# PSU.net
KiCad netlist of a schematic drawn in Altium Designer
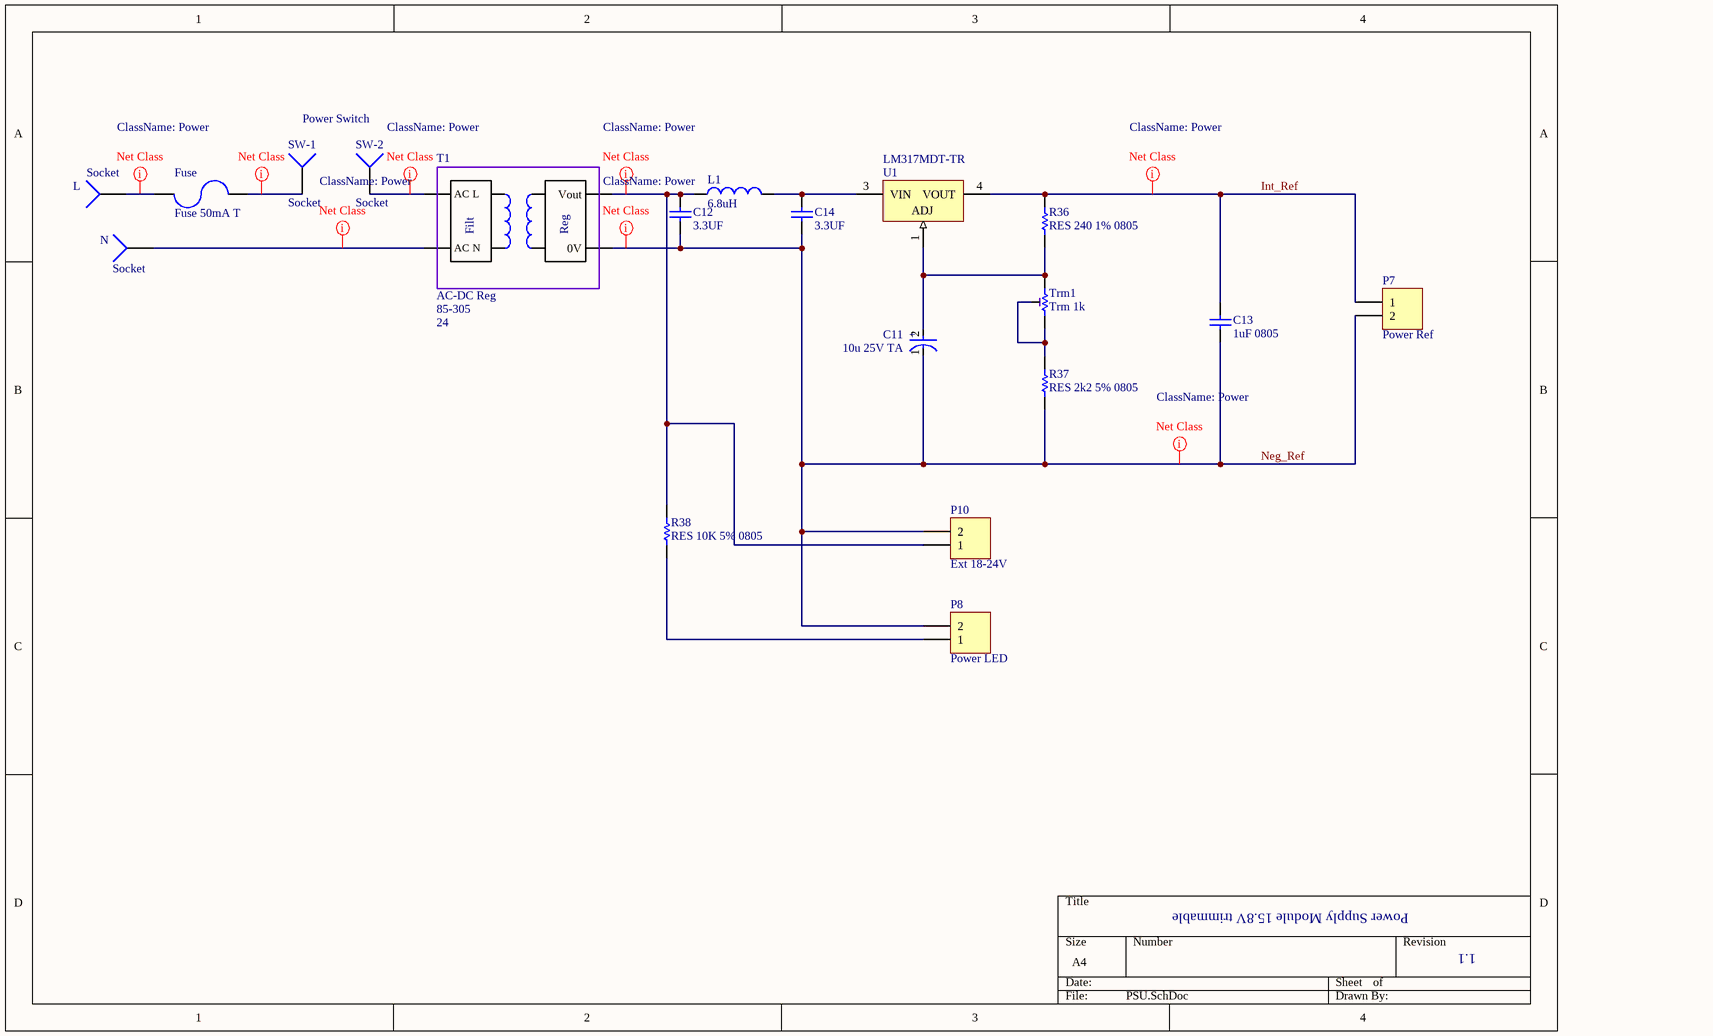
[diagram p0: PSU.SchDoc]

(export (version "E")
  (design (tool "Eeschema 10.0.6"))
  (components
    (comp (ref "C11")
      (value "10u 25V TA")
      (footprint "FP-TPE-D4-MFG")
      (description "CAP TANT 10u 25V")
      (fields (field (name "TOLERANCE") "20%") (field (name "MANUFACTURER PART NUMBER") "6TPE330MAA"))
      (libsource (lib "Altium Content Vault") (part "CMP-05428-000010-1"))
    )
    (comp (ref "C12")
      (value "3.3UF")
      (footprint "CAPC1206(3216)150_L")
      (description "1206 (3216 Metric) Chip Capacitor")
      (libsource (lib "Altium Content Vault") (part "CMP-1590-00001-1"))
    )
    (comp (ref "C13")
      (value "1uF 0805")
      (footprint "CAPC2113X88X50NL30T25")
      (fields (field (name "MANUFACTURER") "Kemet") (field (name "PART NUMBER") "C0805X474K4RACTU"))
      (libsource (lib "Altium Content Vault") (part "CMP-2007-00001-1"))
    )
    (comp (ref "C14")
      (value "3.3UF")
      (footprint "CAPC1206(3216)150_L")
      (description "1206 (3216 Metric) Chip Capacitor")
      (libsource (lib "Altium Content Vault") (part "CMP-1590-00001-1"))
    )
    (comp (ref "Fuse")
      (value "Fuse 50mA T")
      (footprint "Fuse Holder 20mm PCB with Cover")
      (description "Fuse")
      (libsource (lib "Mechanical") (part "Fuse"))
    )
    (comp (ref "L")
      (value "Socket")
      (footprint "PIN1")
      (fields (field (name "PUBLISHER") "Altium Limited"))
      (libsource (lib "Miscellaneous Connectors") (part "Socket"))
    )
    (comp (ref "L1")
      (value "6.8uH")
      (footprint "2.5x2 Inductor")
      (description "Inductor 6.8uH")
      (libsource (lib "Pref Passive") (part "Inductor"))
    )
    (comp (ref "N")
      (value "Socket")
      (footprint "PIN1")
      (fields (field (name "PUBLISHER") "Altium Limited"))
      (libsource (lib "Miscellaneous Connectors") (part "Socket"))
    )
    (comp (ref "P7")
      (value "Power Ref")
      (footprint "HDR1X2")
      (description "Header, 2-Pin")
      (fields (field (name "PUBLISHER") "Altium Limited"))
      (libsource (lib "Miscellaneous Connectors") (part "Header 2"))
    )
    (comp (ref "P8")
      (value "Power LED")
      (footprint "HDR1X2")
      (description "Header, 2-Pin")
      (fields (field (name "PUBLISHER") "Altium Limited"))
      (libsource (lib "") (part "Header 2_1"))
    )
    (comp (ref "P10")
      (value "Ext 18-24V")
      (footprint "HDR1X2")
      (description "Header, 2-Pin")
      (fields (field (name "PUBLISHER") "Altium Limited"))
      (libsource (lib "") (part "Header 2_1"))
    )
    (comp (ref "R36")
      (value "RES 240 1% 0805")
      (footprint "RESC2013X70X40LL20T20")
      (description "Resistor 240 1% 0805  0.2W 10ppm/C")
      (fields (field (name "MANUFACTURER") "Panasonic"))
      (libsource (lib "Altium Content Vault") (part "CMP-2001-00110-5"))
    )
    (comp (ref "R37")
      (value "RES 2k2 5% 0805")
      (footprint "RESC2013X70X40LL20T20")
      (description "Resistor 2k2 5% 0805  0.2W 10ppm/C")
      (fields (field (name "MANUFACTURER") "Panasonic"))
      (libsource (lib "Altium Content Vault") (part "CMP-2001-00110-5"))
    )
    (comp (ref "R38")
      (value "RES 10K 5% 0805")
      (footprint "RESC2013X70X40LL20T20")
      (description "Resistor 10K 5% 0805  0.2W 50ppm/C")
      (fields (field (name "MANUFACTURER") "Panasonic"))
      (libsource (lib "Altium Content Vault") (part "CMP-2001-00110-5"))
    )
    (comp (ref "SW-1")
      (value "Socket")
      (footprint "PIN1")
      (fields (field (name "PUBLISHER") "Altium Limited"))
      (libsource (lib "Miscellaneous Connectors") (part "Socket"))
    )
    (comp (ref "SW-2")
      (value "Socket")
      (footprint "PIN1")
      (fields (field (name "PUBLISHER") "Altium Limited"))
      (libsource (lib "Miscellaneous Connectors") (part "Socket"))
    )
    (comp (ref "T1")
      (value "AC-DC Reg")
      (footprint "IRM-02 Moule SM")
      (description "AC-DC Regulated Module 24V")
      (fields (field (name "VACIN") "85-305") (field (name "VDC OUT") "24"))
      (libsource (lib "Power Module") (part "AC-DC Reg Module"))
    )
    (comp (ref "Trm1")
      (value "Trm 1k")
      (footprint "3214W Trimmer")
      (description "Trimmer")
      (libsource (lib "Pref Passive") (part "Trimmer"))
    )
    (comp (ref "U1")
      (value "LM317MDT-TR")
      (footprint "TO-252_L")
      (description "500mA, Medium Current 1.2 to 37 V Adjustable Voltage Regulator, 3-Pin DPAK, Tape and Reel")
      (libsource (lib "Altium Content Vault") (part "CMP-0244-00074-1"))
    )
  )
  (nets
    (net (code "1") (name "/Int_Ref") (class "Default")
      (node (ref "C13") (pin "1") (pinfunction "1_1") (pintype "passive"))
      (node (ref "P7") (pin "1") (pinfunction "1_1") (pintype "passive"))
      (node (ref "R36") (pin "2") (pinfunction "2_2") (pintype "passive"))
      (node (ref "U1") (pin "4") (pinfunction "VOUT_4") (pintype "power_in"))
    )
    (net (code "2") (name "/Neg_Ref") (class "Default")
      (node (ref "C11") (pin "1") (pinfunction "C_1") (pintype "passive"))
      (node (ref "C12") (pin "1") (pinfunction "1_1") (pintype "passive"))
      (node (ref "C13") (pin "2") (pinfunction "2_2") (pintype "passive"))
      (node (ref "C14") (pin "1") (pinfunction "1_1") (pintype "passive"))
      (node (ref "P10") (pin "2") (pinfunction "2_2") (pintype "passive"))
      (node (ref "P7") (pin "2") (pinfunction "2_2") (pintype "passive"))
      (node (ref "P8") (pin "2") (pinfunction "2_2") (pintype "passive"))
      (node (ref "R37") (pin "1") (pinfunction "1_1") (pintype "passive"))
      (node (ref "T1") (pin "0V") (pinfunction "0V_0V") (pintype "power_in"))
    )
    (net (code "3") (name "Net-(C11-A)") (class "Default")
      (node (ref "C11") (pin "2") (pinfunction "A_2") (pintype "passive"))
      (node (ref "R36") (pin "1") (pinfunction "1_1") (pintype "passive"))
      (node (ref "Trm1") (pin "3") (pinfunction "3_3") (pintype "passive"))
      (node (ref "U1") (pin "1") (pinfunction "ADJ_1") (pintype "input"))
    )
    (net (code "4") (name "Net-(C12-Pad2)") (class "Default")
      (node (ref "C12") (pin "2") (pinfunction "2_2") (pintype "passive"))
      (node (ref "L1") (pin "1") (pinfunction "1_1") (pintype "passive"))
      (node (ref "P10") (pin "1") (pinfunction "1_1") (pintype "passive"))
      (node (ref "R38") (pin "2") (pinfunction "2_2") (pintype "passive"))
      (node (ref "T1") (pin "Vout") (pinfunction "Vout_Vout") (pintype "power_in"))
    )
    (net (code "5") (name "Net-(Fuse-Pad1)") (class "Default")
      (node (ref "Fuse") (pin "1") (pinfunction "1_1") (pintype "passive"))
      (node (ref "L") (pin "1") (pinfunction "1_1") (pintype "passive"))
    )
    (net (code "6") (name "Net-(Fuse-Pad2)") (class "Default")
      (node (ref "Fuse") (pin "2") (pinfunction "2_2") (pintype "passive"))
      (node (ref "SW-1") (pin "1") (pinfunction "1_1") (pintype "passive"))
    )
    (net (code "7") (name "Net-(P8-Pad1)") (class "Default")
      (node (ref "P8") (pin "1") (pinfunction "1_1") (pintype "passive"))
      (node (ref "R38") (pin "1") (pinfunction "1_1") (pintype "passive"))
    )
    (net (code "8") (name "Net-(R37-Pad2)") (class "Default")
      (node (ref "R37") (pin "2") (pinfunction "2_2") (pintype "passive"))
      (node (ref "Trm1") (pin "1") (pinfunction "1_1") (pintype "passive"))
      (node (ref "Trm1") (pin "2") (pinfunction "2_2") (pintype "passive"))
    )
    (net (code "9") (name "Net-(T1-AC_L)") (class "Default")
      (node (ref "SW-2") (pin "1") (pinfunction "1_1") (pintype "passive"))
      (node (ref "T1") (pin "L") (pinfunction "AC_L_L") (pintype "power_in"))
    )
    (net (code "10") (name "Net-(T1-AC_N)") (class "Default")
      (node (ref "N") (pin "1") (pinfunction "1_1") (pintype "passive"))
      (node (ref "T1") (pin "N") (pinfunction "AC_N_N") (pintype "power_in"))
    )
    (net (code "11") (name "Net-(U1-VIN)") (class "Default")
      (node (ref "C14") (pin "2") (pinfunction "2_2") (pintype "passive"))
      (node (ref "L1") (pin "2") (pinfunction "2_2") (pintype "passive"))
      (node (ref "U1") (pin "3") (pinfunction "VIN_3") (pintype "power_in"))
    )
  )
)
